# Min328m.net
KiCad netlist of a schematic drawn in EAGLE
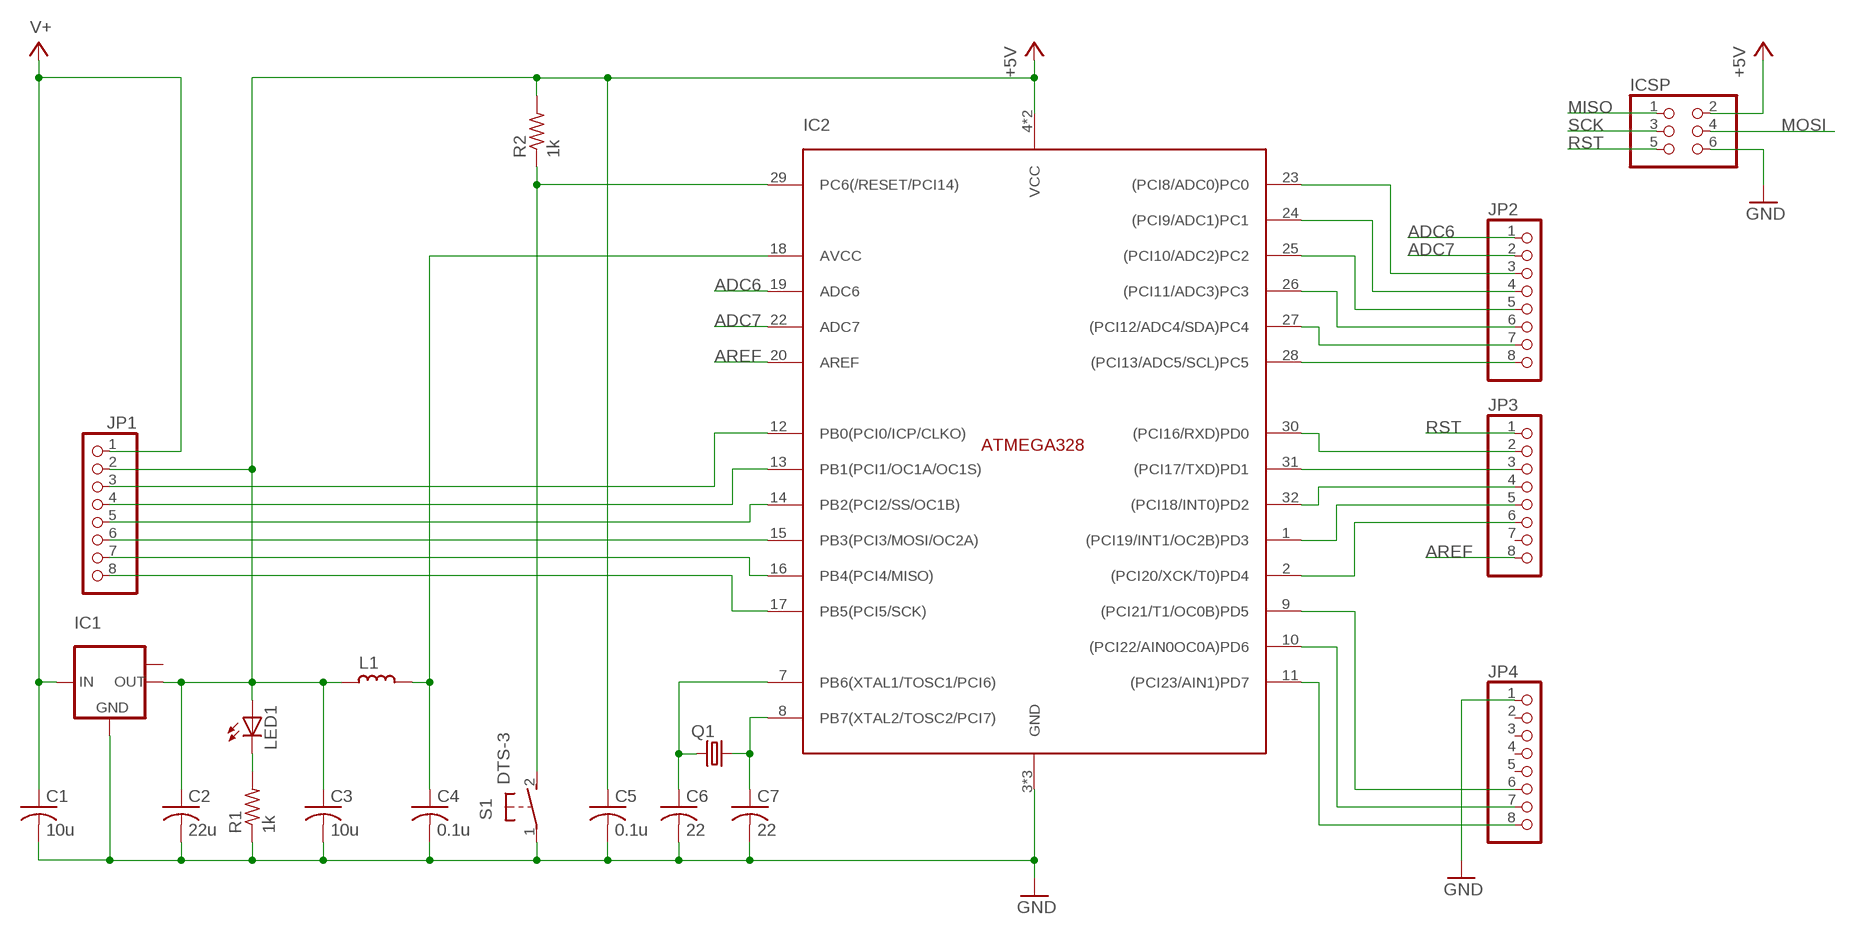
[diagram p0: schematic, sheet 1]

(export (version "E")
  (design (tool "Eeschema 10.0.6"))
  (components
    (comp (ref "C1")
      (value "10u")
      (footprint "eagle-import:C1210K")
      (libsource (lib "eagle-import") (part "C-USC1210K"))
    )
    (comp (ref "C2")
      (value "22u")
      (footprint "eagle-import:C1210K")
      (libsource (lib "eagle-import") (part "C-USC1210K"))
    )
    (comp (ref "C3")
      (value "10u")
      (footprint "eagle-import:C0805K")
      (libsource (lib "eagle-import") (part "C-USC0805K"))
    )
    (comp (ref "C4")
      (value "0.1u")
      (footprint "eagle-import:C0805K")
      (libsource (lib "eagle-import") (part "C-USC0805K"))
    )
    (comp (ref "C5")
      (value "0.1u")
      (footprint "eagle-import:C0805K")
      (libsource (lib "eagle-import") (part "C-USC0805K"))
    )
    (comp (ref "C6")
      (value "22")
      (footprint "eagle-import:C0805K")
      (libsource (lib "eagle-import") (part "C-USC0805K"))
    )
    (comp (ref "C7")
      (value "22")
      (footprint "eagle-import:C0805K")
      (libsource (lib "eagle-import") (part "C-USC0805K"))
    )
    (comp (ref "IC1")
      (value "LM1117MPX-5.0")
      (footprint "eagle-import:SOT223")
      (libsource (lib "eagle-import") (part "LM1117MPX-5.0"))
    )
    (comp (ref "IC2")
      (value "ATMEGA328P")
      (footprint "eagle-import:TQFP32-08")
      (libsource (lib "eagle-import") (part "ATMEGA328P"))
    )
    (comp (ref "ICSP")
      (value "PINHD-2X3")
      (footprint "eagle-import:2X03")
      (libsource (lib "eagle-import") (part "PINHD-2X3"))
    )
    (comp (ref "JP1")
      (value "PINHD-1X8")
      (footprint "eagle-import:1X08")
      (libsource (lib "eagle-import") (part "PINHD-1X8"))
    )
    (comp (ref "JP2")
      (value "PINHD-1X8")
      (footprint "eagle-import:1X08")
      (libsource (lib "eagle-import") (part "PINHD-1X8"))
    )
    (comp (ref "JP3")
      (value "PINHD-1X8")
      (footprint "eagle-import:1X08")
      (libsource (lib "eagle-import") (part "PINHD-1X8"))
    )
    (comp (ref "JP4")
      (value "PINHD-1X8")
      (footprint "eagle-import:1X08")
      (libsource (lib "eagle-import") (part "PINHD-1X8"))
    )
    (comp (ref "L1")
      (value "L_0805")
      (footprint "eagle-import:L0805")
      (libsource (lib "eagle-import") (part "L_0805"))
    )
    (comp (ref "LED1")
      (value "LEDCHIPLED_0805")
      (footprint "eagle-import:CHIPLED_0805")
      (libsource (lib "eagle-import") (part "LEDCHIPLED_0805"))
    )
    (comp (ref "Q1")
      (value "CRYSTALSM49")
      (footprint "eagle-import:SM49")
      (libsource (lib "eagle-import") (part "CRYSTALSM49"))
    )
    (comp (ref "R1")
      (value "1k")
      (footprint "eagle-import:R0805")
      (libsource (lib "eagle-import") (part "R-US_R0805"))
    )
    (comp (ref "R2")
      (value "1k")
      (footprint "eagle-import:R0805")
      (libsource (lib "eagle-import") (part "R-US_R0805"))
    )
    (comp (ref "S1")
      (value "DTS-3")
      (footprint "eagle-import:DTS-3")
      (libsource (lib "eagle-import") (part "DTS-3"))
    )
  )
  (nets
    (net (code "1") (name "+5V") (class "Default")
      (node (ref "C2") (pin "1") (pinfunction "1_1") (pintype "passive"))
      (node (ref "C3") (pin "1") (pinfunction "1_1") (pintype "passive"))
      (node (ref "C5") (pin "1") (pinfunction "1_1") (pintype "passive"))
      (node (ref "IC1") (pin "2") (pinfunction "OUT_2") (pintype "passive"))
      (node (ref "IC2") (pin "4") (pinfunction "VCC_4") (pintype "power_in"))
      (node (ref "IC2") (pin "6") (pinfunction "VCC_6") (pintype "power_in"))
      (node (ref "ICSP") (pin "2") (pinfunction "2_2") (pintype "passive"))
      (node (ref "JP1") (pin "2") (pinfunction "2_2") (pintype "passive"))
      (node (ref "L1") (pin "2") (pinfunction "2_2") (pintype "passive"))
      (node (ref "LED1") (pin "A") (pinfunction "A_A") (pintype "passive"))
      (node (ref "R2") (pin "2") (pinfunction "2_2") (pintype "passive"))
    )
    (net (code "2") (name "/ADC6") (class "Default")
      (node (ref "IC2") (pin "19") (pinfunction "ADC6_19") (pintype "passive"))
      (node (ref "JP2") (pin "1") (pinfunction "1_1") (pintype "passive"))
    )
    (net (code "3") (name "/ADC7") (class "Default")
      (node (ref "IC2") (pin "22") (pinfunction "ADC7_22") (pintype "passive"))
      (node (ref "JP2") (pin "2") (pinfunction "2_2") (pintype "passive"))
    )
    (net (code "4") (name "/AREF") (class "Default")
      (node (ref "IC2") (pin "20") (pinfunction "AREF_20") (pintype "passive"))
      (node (ref "JP3") (pin "8") (pinfunction "8_8") (pintype "passive"))
    )
    (net (code "5") (name "/MISO") (class "Default")
      (node (ref "IC2") (pin "16") (pinfunction "PB4(PCI4/MISO)_16") (pintype "passive"))
      (node (ref "ICSP") (pin "1") (pinfunction "1_1") (pintype "passive"))
      (node (ref "JP1") (pin "7") (pinfunction "7_7") (pintype "passive"))
    )
    (net (code "6") (name "/MOSI") (class "Default")
      (node (ref "IC2") (pin "15") (pinfunction "PB3(PCI3/MOSI/OC2A)_15") (pintype "passive"))
      (node (ref "ICSP") (pin "4") (pinfunction "4_4") (pintype "passive"))
      (node (ref "JP1") (pin "6") (pinfunction "6_6") (pintype "passive"))
    )
    (net (code "7") (name "/RST") (class "Default")
      (node (ref "IC2") (pin "29") (pinfunction "PC6(/RESET/PCI14)_29") (pintype "passive"))
      (node (ref "ICSP") (pin "5") (pinfunction "5_5") (pintype "passive"))
      (node (ref "JP3") (pin "1") (pinfunction "1_1") (pintype "passive"))
      (node (ref "R2") (pin "1") (pinfunction "1_1") (pintype "passive"))
      (node (ref "S1") (pin "2") (pinfunction "2_2") (pintype "passive"))
    )
    (net (code "8") (name "/SCK") (class "Default")
      (node (ref "IC2") (pin "17") (pinfunction "PB5(PCI5/SCK)_17") (pintype "passive"))
      (node (ref "ICSP") (pin "3") (pinfunction "3_3") (pintype "passive"))
      (node (ref "JP1") (pin "8") (pinfunction "8_8") (pintype "passive"))
    )
    (net (code "9") (name "GND") (class "Default")
      (node (ref "C1") (pin "2") (pinfunction "2_2") (pintype "passive"))
      (node (ref "C2") (pin "2") (pinfunction "2_2") (pintype "passive"))
      (node (ref "C3") (pin "2") (pinfunction "2_2") (pintype "passive"))
      (node (ref "C4") (pin "2") (pinfunction "2_2") (pintype "passive"))
      (node (ref "C5") (pin "2") (pinfunction "2_2") (pintype "passive"))
      (node (ref "C6") (pin "2") (pinfunction "2_2") (pintype "passive"))
      (node (ref "C7") (pin "2") (pinfunction "2_2") (pintype "passive"))
      (node (ref "IC1") (pin "1") (pinfunction "GND_1") (pintype "input"))
      (node (ref "IC2") (pin "21") (pinfunction "GND_21") (pintype "power_in"))
      (node (ref "IC2") (pin "3") (pinfunction "GND_3") (pintype "power_in"))
      (node (ref "IC2") (pin "5") (pinfunction "GND_5") (pintype "power_in"))
      (node (ref "ICSP") (pin "6") (pinfunction "6_6") (pintype "passive"))
      (node (ref "JP4") (pin "1") (pinfunction "1_1") (pintype "passive"))
      (node (ref "R1") (pin "1") (pinfunction "1_1") (pintype "passive"))
      (node (ref "S1") (pin "1") (pinfunction "1_1") (pintype "passive"))
    )
    (net (code "10") (name "Net-(IC2-(PCI8{slash}ADC0)PC0)") (class "Default")
      (node (ref "IC2") (pin "23") (pinfunction "(PCI8/ADC0)PC0_23") (pintype "passive"))
      (node (ref "JP2") (pin "3") (pinfunction "3_3") (pintype "passive"))
    )
    (net (code "11") (name "Net-(IC2-(PCI9{slash}ADC1)PC1)") (class "Default")
      (node (ref "IC2") (pin "24") (pinfunction "(PCI9/ADC1)PC1_24") (pintype "passive"))
      (node (ref "JP2") (pin "4") (pinfunction "4_4") (pintype "passive"))
    )
    (net (code "12") (name "Net-(IC2-(PCI10{slash}ADC2)PC2)") (class "Default")
      (node (ref "IC2") (pin "25") (pinfunction "(PCI10/ADC2)PC2_25") (pintype "passive"))
      (node (ref "JP2") (pin "5") (pinfunction "5_5") (pintype "passive"))
    )
    (net (code "13") (name "Net-(IC2-(PCI11{slash}ADC3)PC3)") (class "Default")
      (node (ref "IC2") (pin "26") (pinfunction "(PCI11/ADC3)PC3_26") (pintype "passive"))
      (node (ref "JP2") (pin "6") (pinfunction "6_6") (pintype "passive"))
    )
    (net (code "14") (name "Net-(IC2-(PCI12{slash}ADC4{slash}SDA)PC4)") (class "Default")
      (node (ref "IC2") (pin "27") (pinfunction "(PCI12/ADC4/SDA)PC4_27") (pintype "passive"))
      (node (ref "JP2") (pin "7") (pinfunction "7_7") (pintype "passive"))
    )
    (net (code "15") (name "Net-(IC2-(PCI13{slash}ADC5{slash}SCL)PC5)") (class "Default")
      (node (ref "IC2") (pin "28") (pinfunction "(PCI13/ADC5/SCL)PC5_28") (pintype "passive"))
      (node (ref "JP2") (pin "8") (pinfunction "8_8") (pintype "passive"))
    )
    (net (code "16") (name "Net-(IC2-(PCI16{slash}RXD)PD0)") (class "Default")
      (node (ref "IC2") (pin "30") (pinfunction "(PCI16/RXD)PD0_30") (pintype "passive"))
      (node (ref "JP3") (pin "2") (pinfunction "2_2") (pintype "passive"))
    )
    (net (code "17") (name "Net-(IC2-(PCI17{slash}TXD)PD1)") (class "Default")
      (node (ref "IC2") (pin "31") (pinfunction "(PCI17/TXD)PD1_31") (pintype "passive"))
      (node (ref "JP3") (pin "3") (pinfunction "3_3") (pintype "passive"))
    )
    (net (code "18") (name "Net-(IC2-(PCI18{slash}INT0)PD2)") (class "Default")
      (node (ref "IC2") (pin "32") (pinfunction "(PCI18/INT0)PD2_32") (pintype "passive"))
      (node (ref "JP3") (pin "4") (pinfunction "4_4") (pintype "passive"))
    )
    (net (code "19") (name "Net-(IC2-(PCI19{slash}INT1{slash}OC2B)PD3)") (class "Default")
      (node (ref "IC2") (pin "1") (pinfunction "(PCI19/INT1/OC2B)PD3_1") (pintype "passive"))
      (node (ref "JP3") (pin "5") (pinfunction "5_5") (pintype "passive"))
    )
    (net (code "20") (name "Net-(IC2-(PCI20{slash}XCK{slash}T0)PD4)") (class "Default")
      (node (ref "IC2") (pin "2") (pinfunction "(PCI20/XCK/T0)PD4_2") (pintype "passive"))
      (node (ref "JP3") (pin "6") (pinfunction "6_6") (pintype "passive"))
    )
    (net (code "21") (name "Net-(IC2-(PCI21{slash}T1{slash}OC0B)PD5)") (class "Default")
      (node (ref "IC2") (pin "9") (pinfunction "(PCI21/T1/OC0B)PD5_9") (pintype "passive"))
      (node (ref "JP4") (pin "6") (pinfunction "6_6") (pintype "passive"))
    )
    (net (code "22") (name "Net-(IC2-(PCI22{slash}AIN0OC0A)PD6)") (class "Default")
      (node (ref "IC2") (pin "10") (pinfunction "(PCI22/AIN0OC0A)PD6_10") (pintype "passive"))
      (node (ref "JP4") (pin "7") (pinfunction "7_7") (pintype "passive"))
    )
    (net (code "23") (name "Net-(IC2-(PCI23{slash}AIN1)PD7)") (class "Default")
      (node (ref "IC2") (pin "11") (pinfunction "(PCI23/AIN1)PD7_11") (pintype "passive"))
      (node (ref "JP4") (pin "8") (pinfunction "8_8") (pintype "passive"))
    )
    (net (code "24") (name "Net-(IC2-AVCC)") (class "Default")
      (node (ref "C4") (pin "1") (pinfunction "1_1") (pintype "passive"))
      (node (ref "IC2") (pin "18") (pinfunction "AVCC_18") (pintype "power_in"))
      (node (ref "L1") (pin "1") (pinfunction "1_1") (pintype "passive"))
    )
    (net (code "25") (name "Net-(IC2-PB0(PCI0{slash}ICP{slash}CLKO))") (class "Default")
      (node (ref "IC2") (pin "12") (pinfunction "PB0(PCI0/ICP/CLKO)_12") (pintype "passive"))
      (node (ref "JP1") (pin "3") (pinfunction "3_3") (pintype "passive"))
    )
    (net (code "26") (name "Net-(IC2-PB1(PCI1{slash}OC1A{slash}OC1S))") (class "Default")
      (node (ref "IC2") (pin "13") (pinfunction "PB1(PCI1/OC1A/OC1S)_13") (pintype "passive"))
      (node (ref "JP1") (pin "4") (pinfunction "4_4") (pintype "passive"))
    )
    (net (code "27") (name "Net-(IC2-PB2(PCI2{slash}SS{slash}OC1B))") (class "Default")
      (node (ref "IC2") (pin "14") (pinfunction "PB2(PCI2/SS/OC1B)_14") (pintype "passive"))
      (node (ref "JP1") (pin "5") (pinfunction "5_5") (pintype "passive"))
    )
    (net (code "28") (name "Net-(IC2-PB6(XTAL1{slash}TOSC1{slash}PCI6))") (class "Default")
      (node (ref "C6") (pin "1") (pinfunction "1_1") (pintype "passive"))
      (node (ref "IC2") (pin "7") (pinfunction "PB6(XTAL1/TOSC1/PCI6)_7") (pintype "passive"))
      (node (ref "Q1") (pin "2") (pinfunction "2_2") (pintype "passive"))
    )
    (net (code "29") (name "Net-(IC2-PB7(XTAL2{slash}TOSC2{slash}PCI7))") (class "Default")
      (node (ref "C7") (pin "1") (pinfunction "1_1") (pintype "passive"))
      (node (ref "IC2") (pin "8") (pinfunction "PB7(XTAL2/TOSC2/PCI7)_8") (pintype "passive"))
      (node (ref "Q1") (pin "1") (pinfunction "1_1") (pintype "passive"))
    )
    (net (code "30") (name "Net-(LED1-PadC)") (class "Default")
      (node (ref "LED1") (pin "C") (pinfunction "C_C") (pintype "passive"))
      (node (ref "R1") (pin "2") (pinfunction "2_2") (pintype "passive"))
    )
    (net (code "31") (name "V+") (class "Default")
      (node (ref "C1") (pin "1") (pinfunction "1_1") (pintype "passive"))
      (node (ref "IC1") (pin "3") (pinfunction "IN_3") (pintype "input"))
      (node (ref "JP1") (pin "1") (pinfunction "1_1") (pintype "passive"))
    )
    (net (code "32") (name "unconnected-(IC1-OUT1-PadTAB)") (class "Default")
      (node (ref "IC1") (pin "TAB") (pinfunction "OUT1_TAB") (pintype "passive"))
    )
    (net (code "33") (name "unconnected-(JP3-Pad7)") (class "Default")
      (node (ref "JP3") (pin "7") (pinfunction "7_7") (pintype "passive"))
    )
    (net (code "34") (name "unconnected-(JP4-Pad2)") (class "Default")
      (node (ref "JP4") (pin "2") (pinfunction "2_2") (pintype "passive"))
    )
    (net (code "35") (name "unconnected-(JP4-Pad3)") (class "Default")
      (node (ref "JP4") (pin "3") (pinfunction "3_3") (pintype "passive"))
    )
    (net (code "36") (name "unconnected-(JP4-Pad4)") (class "Default")
      (node (ref "JP4") (pin "4") (pinfunction "4_4") (pintype "passive"))
    )
    (net (code "37") (name "unconnected-(JP4-Pad5)") (class "Default")
      (node (ref "JP4") (pin "5") (pinfunction "5_5") (pintype "passive"))
    )
  )
)
